# MCU-ADDON.net
KiCad netlist of a schematic drawn in Altium Designer
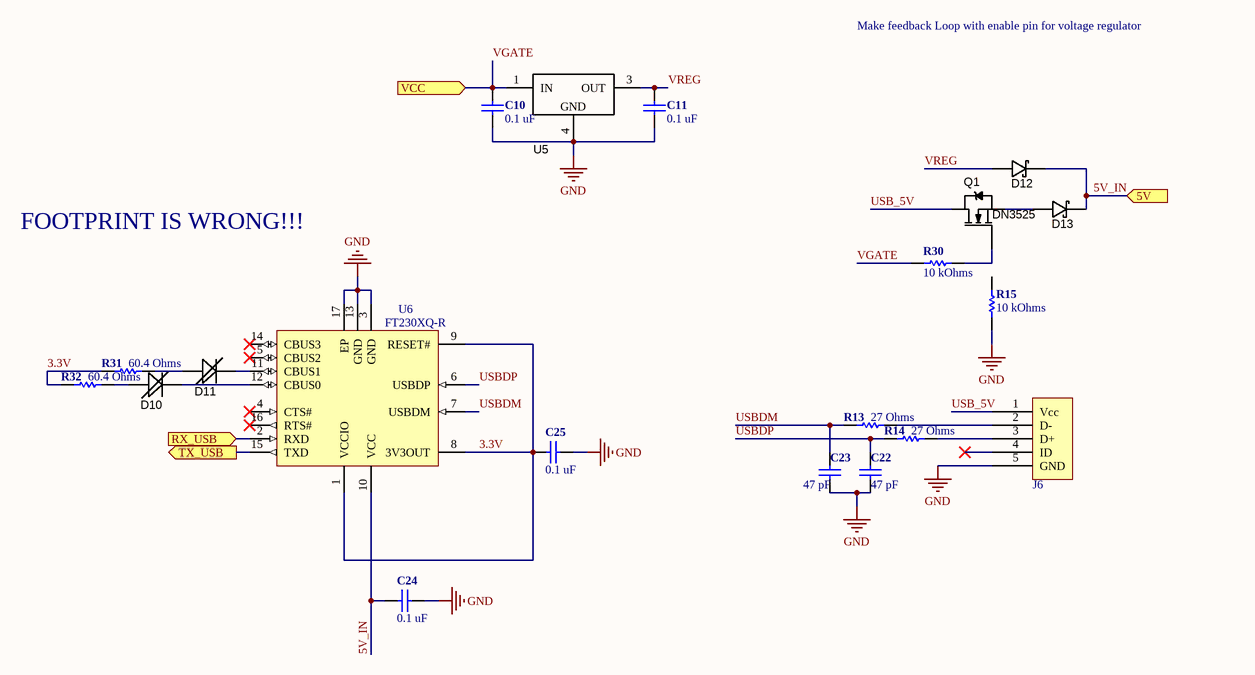
[diagram p0: MCU-ADDON.SchDoc]

(export (version "E")
  (design (tool "Eeschema 10.0.6"))
  (components
    (comp (ref "C10")
      (value "0.1 uF")
      (footprint "CAP-0402(1005)-R")
      (description "CAP CER 0.1 UF 16V 5% X7R 0402")
      (fields
        (field (name "MANUFACTURER") "Yageo")
        (field (name "MANUFACTURER PART NUMBER") "CC0402KRX7R7BB104")
      )
      (libsource (lib "CarlLibrary") (part "CAP- 0.1 uF- 16 V-CER-0402(1005)"))
    )
    (comp (ref "C11")
      (value "0.1 uF")
      (footprint "CAP-0402(1005)-R")
      (description "CAP CER 0.1 UF 16V 5% X7R 0402")
      (fields
        (field (name "MANUFACTURER") "Yageo")
        (field (name "MANUFACTURER PART NUMBER") "CC0402KRX7R7BB104")
      )
      (libsource (lib "CarlLibrary") (part "CAP- 0.1 uF- 16 V-CER-0402(1005)"))
    )
    (comp (ref "C22")
      (value "47 pF")
      (footprint "CAP-0603(1608)-R")
      (description "CAP CER 47 pF 50V 5% C0G 0603")
      (fields (field (name "TOLERANCE") "5 %") (field (name "MANUFACTURER") "Yageo"))
      (libsource (lib "CarlLibrary") (part "CAP- 47 pF- 50 V-CER-0603(1608)"))
    )
    (comp (ref "C23")
      (value "47 pF")
      (footprint "CAP-0603(1608)-R")
      (description "CAP CER 47 pF 50V 5% C0G 0603")
      (fields (field (name "TOLERANCE") "5 %") (field (name "MANUFACTURER") "Yageo"))
      (libsource (lib "CarlLibrary") (part "CAP- 47 pF- 50 V-CER-0603(1608)"))
    )
    (comp (ref "C24")
      (value "0.1 uF")
      (footprint "CAP-0402(1005)-R")
      (description "CAP CER 0.1 UF 16V 5% X7R 0402")
      (fields (field (name "TOLERANCE") "10 %") (field (name "MANUFACTURER") "Yageo"))
      (libsource (lib "CarlLibrary") (part "CAP- 0.1 uF- 16 V-CER-0402(1005)"))
    )
    (comp (ref "C25")
      (value "0.1 uF")
      (footprint "CAP-0402(1005)-R")
      (description "CAP CER 0.1 UF 16V 5% X7R 0402")
      (fields (field (name "TOLERANCE") "10 %") (field (name "MANUFACTURER") "Yageo"))
      (libsource (lib "CarlLibrary") (part "CAP- 0.1 uF- 16 V-CER-0402(1005)"))
    )
    (comp (ref "D10")
      (value "Red")
      (footprint "LED-1206")
      (description "LED, 0805 SMD, Red")
      (fields
        (field (name "MANUFACTURER") "Kingbright")
        (field (name "MANUFACTURER PART NUMBER") "APTD3216SURCK")
      )
      (libsource (lib "CarlLibrary") (part "LED_SMD_RED_0805"))
    )
    (comp (ref "D11")
      (value "Red")
      (footprint "LED-1206")
      (description "LED, 0805 SMD, Red")
      (fields
        (field (name "MANUFACTURER") "Kingbright")
        (field (name "MANUFACTURER PART NUMBER") "APTD3216SURCK")
      )
      (libsource (lib "CarlLibrary") (part "LED_SMD_RED_0805"))
    )
    (comp (ref "D12")
      (value "MBR120VLSFT3G")
      (footprint "SOD-123FL")
      (description "Diode Schottky SMD 20V 1A SMD")
      (fields (field (name "MANUFACTURER") "ON Semiconductor"))
      (libsource (lib "CarlLibrary") (part "DIODE_SCHOTTKY"))
    )
    (comp (ref "D13")
      (value "MBR120VLSFT3G")
      (footprint "SOD-123FL")
      (description "Diode Schottky SMD 20V 1A SMD")
      (fields (field (name "MANUFACTURER") "ON Semiconductor"))
      (libsource (lib "CarlLibrary") (part "DIODE_SCHOTTKY"))
    )
    (comp (ref "J6")
      (value "USB")
      (footprint "USB_Connector_5P_MICRO_USB_FCI")
      (description "USB_Connector_5P_MICRO_USB_FCI")
      (fields (field (name "MANUFACTURER") "FCI") (field (name "MANUFACTURER PART NUMBER") "10118194-0001LF"))
      (libsource (lib "MasterLibrary") (part "USB"))
    )
    (comp (ref "Q1")
      (value "DN3525")
      (footprint "SOT89-3")
      (description "MOSFET N-Channel DEPLETION SMD")
      (fields
        (field (name "MANUFACTURER") "Microchip Technology")
        (field (name "MANUFACTURER PART NUMBER") "DN3525N8-G")
      )
      (libsource (lib "CarlLibrary") (part "DN3525N8-G"))
    )
    (comp (ref "R13")
      (value "27 Ohms")
      (footprint "R-0603(1608)-R")
      (description "RES 27 OHM 100 mW  SMD")
      (fields
        (field (name "MANUFACTURER") "Yageo")
        (field (name "MANUFACTURER PART NUMBER") "RC0603JR-0727RL")
      )
      (libsource (lib "CarlLibrary") (part "R-27-100 mW-0603"))
    )
    (comp (ref "R14")
      (value "27 Ohms")
      (footprint "R-0603(1608)-R")
      (description "RES 27 OHM 100 mW  SMD")
      (fields
        (field (name "MANUFACTURER") "Yageo")
        (field (name "MANUFACTURER PART NUMBER") "RC0603JR-0727RL")
      )
      (libsource (lib "CarlLibrary") (part "R-27-100 mW-0603"))
    )
    (comp (ref "R15")
      (value "10 kOhms")
      (footprint "R-0603(1608)-R")
      (description "RES 10k OHM 1/10W 0603 SMD")
      (fields
        (field (name "MANUFACTURER") "Yageo")
        (field (name "MANUFACTURER PART NUMBER") "RC0603FR-0710KL")
      )
      (libsource (lib "CarlLibrary") (part "R-10k-100mW-0603"))
    )
    (comp (ref "R30")
      (value "10 kOhms")
      (footprint "R-0603(1608)-R")
      (description "RES 10k OHM 1/10W 0603 SMD")
      (fields
        (field (name "MANUFACTURER") "Yageo")
        (field (name "MANUFACTURER PART NUMBER") "RC0603FR-0710KL")
      )
      (libsource (lib "CarlLibrary") (part "R-10k-100mW-0603"))
    )
    (comp (ref "R31")
      (value "60.4 Ohms")
      (footprint "R-0603(1608)-R")
      (description "RES 60.4 OHM 100 mW  SMD")
      (fields
        (field (name "MANUFACTURER") "Yageo")
        (field (name "MANUFACTURER PART NUMBER") "RC0603FR-0760R4L")
      )
      (libsource (lib "CarlLibrary") (part "R-60.4-100mW-0805"))
    )
    (comp (ref "R32")
      (value "60.4 Ohms")
      (footprint "R-0603(1608)-R")
      (description "RES 60.4 OHM 100 mW  SMD")
      (fields
        (field (name "MANUFACTURER") "Yageo")
        (field (name "MANUFACTURER PART NUMBER") "RC0603FR-0760R4L")
      )
      (libsource (lib "CarlLibrary") (part "R-60.4-100mW-0805"))
    )
    (comp (ref "U5")
      (value "FIXED 5V")
      (footprint "TO-252")
      (description "Voltage Regulator IC, DPAK SMD, MC78M05CDTRKG")
      (fields
        (field (name "MANUFACTURER") "ON Semiconductor")
        (field (name "MANUFACTURER PART NUMBER") "MC78M05CDTRKG")
      )
      (libsource (lib "CarlLibrary") (part "MC78M05CDTRKG"))
    )
    (comp (ref "U6")
      (value "FT230XQ-R")
      (footprint "QFN-16")
      (fields (field (name "MANUFACTURER") "FTDI"))
      (libsource (lib "CarlLibrary") (part "FT230XQ-R"))
    )
  )
  (nets
    (net (code "1") (name "/3.3V") (class "Default")
      (node (ref "C25") (pin "1") (pinfunction "1_1") (pintype "passive"))
      (node (ref "R31") (pin "1") (pinfunction "1_1") (pintype "passive"))
      (node (ref "R32") (pin "1") (pinfunction "1_1") (pintype "passive"))
      (node (ref "U6") (pin "1") (pinfunction "VCCIO_1") (pintype "power_in"))
      (node (ref "U6") (pin "8") (pinfunction "3V3OUT_8") (pintype "power_in"))
      (node (ref "U6") (pin "9") (pinfunction "RESET#_9") (pintype "passive"))
    )
    (net (code "2") (name "/5V_IN") (class "Default")
      (node (ref "C24") (pin "1") (pinfunction "1_1") (pintype "passive"))
      (node (ref "D12") (pin "K") (pinfunction "K_K") (pintype "passive"))
      (node (ref "D13") (pin "K") (pinfunction "K_K") (pintype "passive"))
      (node (ref "U6") (pin "10") (pinfunction "VCC_10") (pintype "power_in"))
    )
    (net (code "3") (name "/RX_USB") (class "Default")
      (node (ref "U6") (pin "2") (pinfunction "RXD_2") (pintype "input"))
    )
    (net (code "4") (name "/TX_USB") (class "Default")
      (node (ref "U6") (pin "15") (pinfunction "TXD_15") (pintype "output"))
    )
    (net (code "5") (name "/USBDM") (class "Default")
      (node (ref "C23") (pin "1") (pinfunction "1_1") (pintype "passive"))
      (node (ref "R13") (pin "1") (pinfunction "1_1") (pintype "passive"))
      (node (ref "U6") (pin "7") (pinfunction "USBDM_7") (pintype "input"))
    )
    (net (code "6") (name "/USBDP") (class "Default")
      (node (ref "C22") (pin "1") (pinfunction "1_1") (pintype "passive"))
      (node (ref "R14") (pin "1") (pinfunction "1_1") (pintype "passive"))
      (node (ref "U6") (pin "6") (pinfunction "USBDP_6") (pintype "input"))
    )
    (net (code "7") (name "/USB_5V") (class "Default")
      (node (ref "J6") (pin "1") (pinfunction "Vcc_1") (pintype "passive"))
      (node (ref "Q1") (pin "2") (pinfunction "D_2") (pintype "passive"))
    )
    (net (code "8") (name "/VGATE") (class "Default")
      (node (ref "C10") (pin "1") (pinfunction "1_1") (pintype "passive"))
      (node (ref "R30") (pin "1") (pinfunction "1_1") (pintype "passive"))
      (node (ref "U5") (pin "1") (pinfunction "IN_1") (pintype "passive"))
    )
    (net (code "9") (name "/VREG") (class "Default")
      (node (ref "C11") (pin "1") (pinfunction "1_1") (pintype "passive"))
      (node (ref "D12") (pin "A") (pinfunction "A_A") (pintype "passive"))
      (node (ref "U5") (pin "3") (pinfunction "OUT_3") (pintype "power_in"))
    )
    (net (code "10") (name "GND") (class "Default")
      (node (ref "C10") (pin "2") (pinfunction "2_2") (pintype "passive"))
      (node (ref "C11") (pin "2") (pinfunction "2_2") (pintype "passive"))
      (node (ref "C22") (pin "2") (pinfunction "2_2") (pintype "passive"))
      (node (ref "C23") (pin "2") (pinfunction "2_2") (pintype "passive"))
      (node (ref "C24") (pin "2") (pinfunction "2_2") (pintype "passive"))
      (node (ref "C25") (pin "2") (pinfunction "2_2") (pintype "passive"))
      (node (ref "J6") (pin "5") (pinfunction "GND_5") (pintype "passive"))
      (node (ref "R15") (pin "1") (pinfunction "1_1") (pintype "passive"))
      (node (ref "U5") (pin "4") (pinfunction "GND_4") (pintype "power_in"))
      (node (ref "U6") (pin "13") (pinfunction "GND_13") (pintype "power_in"))
      (node (ref "U6") (pin "17") (pinfunction "EP_17") (pintype "power_in"))
      (node (ref "U6") (pin "3") (pinfunction "GND_3") (pintype "power_in"))
    )
    (net (code "11") (name "Net-(D10-PadA)") (class "Default")
      (node (ref "D10") (pin "A") (pinfunction "A_A") (pintype "passive"))
      (node (ref "R32") (pin "2") (pinfunction "2_2") (pintype "passive"))
    )
    (net (code "12") (name "Net-(D11-PadA)") (class "Default")
      (node (ref "D11") (pin "A") (pinfunction "A_A") (pintype "passive"))
      (node (ref "R31") (pin "2") (pinfunction "2_2") (pintype "passive"))
    )
    (net (code "13") (name "Net-(J6-D+)") (class "Default")
      (node (ref "J6") (pin "3") (pinfunction "D+_3") (pintype "passive"))
      (node (ref "R14") (pin "2") (pinfunction "2_2") (pintype "passive"))
    )
    (net (code "14") (name "Net-(J6-D-)") (class "Default")
      (node (ref "J6") (pin "2") (pinfunction "D-_2") (pintype "passive"))
      (node (ref "R13") (pin "2") (pinfunction "2_2") (pintype "passive"))
    )
    (net (code "15") (name "Net-(Q1-G)") (class "Default")
      (node (ref "Q1") (pin "1") (pinfunction "G_1") (pintype "passive"))
      (node (ref "R30") (pin "2") (pinfunction "2_2") (pintype "passive"))
    )
    (net (code "16") (name "Net-(Q1-S)") (class "Default")
      (node (ref "D13") (pin "A") (pinfunction "A_A") (pintype "passive"))
      (node (ref "Q1") (pin "3") (pinfunction "S_3") (pintype "passive"))
    )
    (net (code "17") (name "Net-(U6-CBUS0)") (class "Default")
      (node (ref "D10") (pin "K") (pinfunction "K_K") (pintype "passive"))
      (node (ref "U6") (pin "12") (pinfunction "CBUS0_12") (pintype "bidirectional"))
    )
    (net (code "18") (name "Net-(U6-CBUS1)") (class "Default")
      (node (ref "D11") (pin "K") (pinfunction "K_K") (pintype "passive"))
      (node (ref "U6") (pin "11") (pinfunction "CBUS1_11") (pintype "bidirectional"))
    )
    (net (code "19") (name "unconnected-(J6-ID-Pad4)") (class "Default")
      (node (ref "J6") (pin "4") (pinfunction "ID_4") (pintype "passive+no_connect"))
    )
    (net (code "20") (name "unconnected-(R15-Pad2)") (class "Default")
      (node (ref "R15") (pin "2") (pinfunction "2_2") (pintype "passive"))
    )
    (net (code "21") (name "unconnected-(U6-CBUS2-Pad5)") (class "Default")
      (node (ref "U6") (pin "5") (pinfunction "CBUS2_5") (pintype "bidirectional+no_connect"))
    )
    (net (code "22") (name "unconnected-(U6-CBUS3-Pad14)") (class "Default")
      (node (ref "U6") (pin "14") (pinfunction "CBUS3_14") (pintype "bidirectional+no_connect"))
    )
    (net (code "23") (name "unconnected-(U6-CTS#-Pad4)") (class "Default")
      (node (ref "U6") (pin "4") (pinfunction "CTS#_4") (pintype "input+no_connect"))
    )
    (net (code "24") (name "unconnected-(U6-RTS#-Pad16)") (class "Default")
      (node (ref "U6") (pin "16") (pinfunction "RTS#_16") (pintype "output+no_connect"))
    )
  )
)
